# NILINET_RFT.net
KiCad netlist of a schematic drawn in Altium Designer
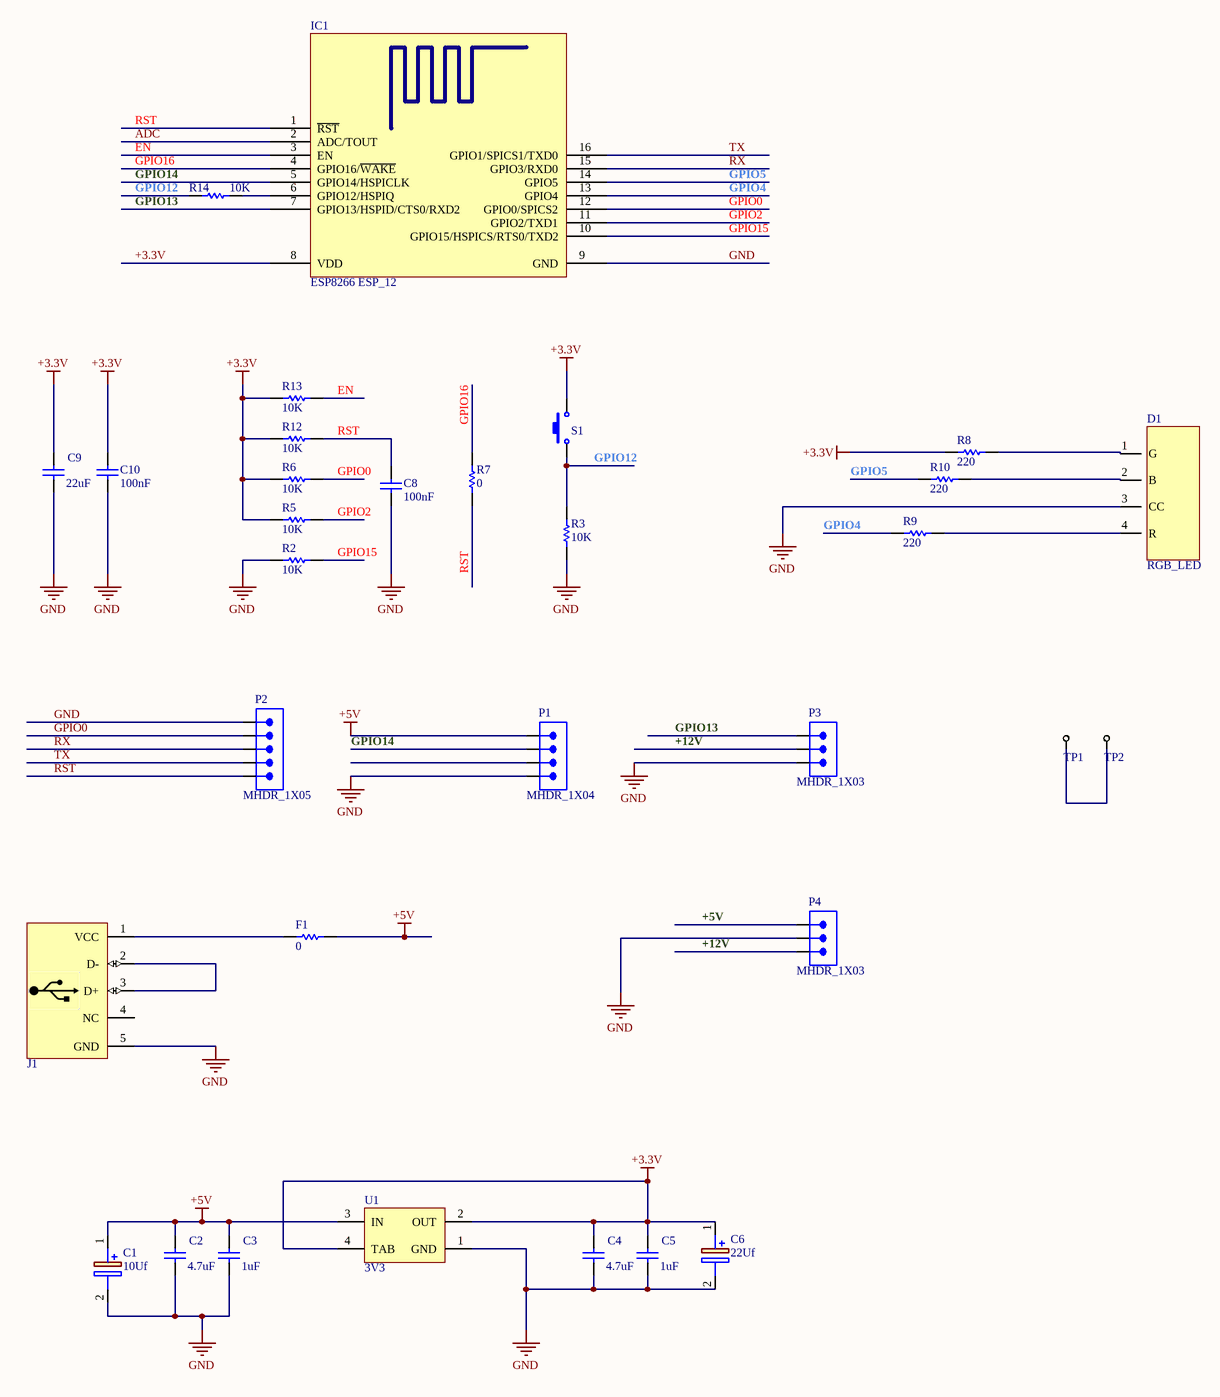
[diagram p0: NILINET_RFT.SchDoc]

(export (version "E")
  (design (tool "Eeschema 10.0.6"))
  (components
    (comp (ref "C1")
      (value "10Uf")
      (footprint "SamacSys:UWT(4X5.4)")
      (description "Capacitor Polarised")
      (fields
        (field (name "MANUFACTURER_PART_NUMBER") "UWT1C100MCL1GB")
        (field (name "MOUSER PART NUMBER") "647-UWT1C100MCL1B")
      )
      (libsource (lib "*") (part "UWT1C100MCL1GB"))
    )
    (comp (ref "C2")
      (value "4.7uF")
      (footprint "CAP0805")
      (description "TOTAL CAPACITOR SMD PACK")
      (fields (field (name "DESIGNER") "Abbas Basereh"))
      (libsource (lib "Altium") (part "CAP SMD PACKAGE"))
    )
    (comp (ref "C3")
      (value "1uF")
      (footprint "CAP0805")
      (description "TOTAL CAPACITOR SMD PACK")
      (fields (field (name "DESIGNER") "Abbas Basereh"))
      (libsource (lib "Altium") (part "CAP SMD PACKAGE"))
    )
    (comp (ref "C4")
      (value "4.7uF")
      (footprint "CAP0805")
      (description "TOTAL CAPACITOR SMD PACK")
      (fields (field (name "DESIGNER") "Abbas Basereh"))
      (libsource (lib "Altium") (part "CAP SMD PACKAGE"))
    )
    (comp (ref "C5")
      (value "1uF")
      (footprint "CAP0805")
      (description "TOTAL CAPACITOR SMD PACK")
      (fields (field (name "DESIGNER") "Abbas Basereh"))
      (libsource (lib "Altium") (part "CAP SMD PACKAGE"))
    )
    (comp (ref "C6")
      (value "22Uf")
      (footprint "SamacSys:UWT(4X5.4)")
      (description "Capacitor Polarised")
      (fields
        (field (name "MANUFACTURER_PART_NUMBER") "UWT1C100MCL1GB")
        (field (name "MOUSER PART NUMBER") "647-UWT1C100MCL1B")
      )
      (libsource (lib "*") (part "UWT1C100MCL1GB"))
    )
    (comp (ref "C8")
      (value "100nF")
      (footprint "CAP0805")
      (description "TOTAL CAPACITOR SMD PACK")
      (fields (field (name "DESIGNER") "Abbas Basereh"))
      (libsource (lib "Altium") (part "CAP SMD PACKAGE"))
    )
    (comp (ref "C9")
      (value "22uF")
      (footprint "CAP0805")
      (description "TOTAL CAPACITOR SMD PACK")
      (fields (field (name "DESIGNER") "Abbas Basereh"))
      (libsource (lib "Altium") (part "CAP SMD PACKAGE"))
    )
    (comp (ref "C10")
      (value "100nF")
      (footprint "CAP0805")
      (description "TOTAL CAPACITOR SMD PACK")
      (fields (field (name "DESIGNER") "Abbas Basereh"))
      (libsource (lib "Altium") (part "CAP SMD PACKAGE"))
    )
    (comp (ref "D1") (value "RGB_LED") (footprint "RGB_LED") (libsource (lib "RGB_LED") (part "RGB_LED")))
    (comp (ref "F1")
      (value "0")
      (footprint "RES0805")
      (description "TOTAL SMD RESISTOR PACK")
      (fields (field (name "DESIGNER") "Abbas Basereh"))
      (libsource (lib "Altium") (part "RES SMD PACKAGE"))
    )
    (comp (ref "IC1")
      (value "ESP8266 ESP_12")
      (footprint "ESP8266 ESP_12")
      (description "ESP8266 ESP-12")
      (fields (field (name "PUBLISHER") "Cynetik Group") (field (name "LATESTREVIEWER") "Zion Blue"))
      (libsource (lib "ESP8266") (part "ESP8266 ESP_12"))
    )
    (comp (ref "J1")
      (value "USB Connector")
      (footprint "MicroUSB111")
      (description "USB Connector MICRO-B Type")
      (fields (field (name "DESIGNER") "ABBAS BASEREH") (field (name "PUBLISHER") "ABBAS BASEREH"))
      (libsource (lib "Altium") (part "USB MICRO"))
    )
    (comp (ref "P1")
      (value "MHDR_1X04")
      (footprint "MHDR1X04-254P")
      (description "Male Header 1X04")
      (libsource (lib "Sockets And Connectors") (part "MHDR_1X04"))
    )
    (comp (ref "P2")
      (value "MHDR_1X05")
      (footprint "MHDR1X05-254P")
      (description "Male Header 1X05")
      (libsource (lib "Sockets And Connectors") (part "MHDR_1X05"))
    )
    (comp (ref "P3")
      (value "MHDR_1X03")
      (footprint "MHDR1X03-254P")
      (description "Male Header 1X03")
      (libsource (lib "Sockets And Connectors") (part "MHDR_1X03"))
    )
    (comp (ref "P4")
      (value "MHDR_1X03")
      (footprint "MHDR1X03-254P")
      (description "Male Header 1X03")
      (libsource (lib "Sockets And Connectors") (part "MHDR_1X03"))
    )
    (comp (ref "R2")
      (value "10K")
      (footprint "RES0805")
      (description "TOTAL SMD RESISTOR PACK")
      (fields (field (name "DESIGNER") "Abbas Basereh"))
      (libsource (lib "Altium") (part "RES SMD PACKAGE"))
    )
    (comp (ref "R3")
      (value "10K")
      (footprint "RES0805")
      (description "TOTAL SMD RESISTOR PACK")
      (fields (field (name "DESIGNER") "Abbas Basereh"))
      (libsource (lib "Altium") (part "RES SMD PACKAGE"))
    )
    (comp (ref "R5")
      (value "10K")
      (footprint "RES0805")
      (description "TOTAL SMD RESISTOR PACK")
      (fields (field (name "DESIGNER") "Abbas Basereh"))
      (libsource (lib "Altium") (part "RES SMD PACKAGE"))
    )
    (comp (ref "R6")
      (value "10K")
      (footprint "RES0805")
      (description "TOTAL SMD RESISTOR PACK")
      (fields (field (name "DESIGNER") "Abbas Basereh"))
      (libsource (lib "Altium") (part "RES SMD PACKAGE"))
    )
    (comp (ref "R7")
      (value "0")
      (footprint "RES0805")
      (description "TOTAL SMD RESISTOR PACK")
      (fields (field (name "DESIGNER") "Abbas Basereh"))
      (libsource (lib "Altium") (part "RES SMD PACKAGE"))
    )
    (comp (ref "R8")
      (value "220")
      (footprint "RES0805")
      (description "TOTAL SMD RESISTOR PACK")
      (fields (field (name "DESIGNER") "Abbas Basereh"))
      (libsource (lib "Altium") (part "RES SMD PACKAGE"))
    )
    (comp (ref "R9")
      (value "220")
      (footprint "RES0805")
      (description "TOTAL SMD RESISTOR PACK")
      (fields (field (name "DESIGNER") "Abbas Basereh"))
      (libsource (lib "Altium") (part "RES SMD PACKAGE"))
    )
    (comp (ref "R10")
      (value "220")
      (footprint "RES0805")
      (description "TOTAL SMD RESISTOR PACK")
      (fields (field (name "DESIGNER") "Abbas Basereh"))
      (libsource (lib "Altium") (part "RES SMD PACKAGE"))
    )
    (comp (ref "R12")
      (value "10K")
      (footprint "RES0805")
      (description "TOTAL SMD RESISTOR PACK")
      (fields (field (name "DESIGNER") "Abbas Basereh"))
      (libsource (lib "Altium") (part "RES SMD PACKAGE"))
    )
    (comp (ref "R13")
      (value "10K")
      (footprint "RES0805")
      (description "TOTAL SMD RESISTOR PACK")
      (fields (field (name "DESIGNER") "Abbas Basereh"))
      (libsource (lib "Altium") (part "RES SMD PACKAGE"))
    )
    (comp (ref "R14")
      (value "10K")
      (footprint "RES0805")
      (description "TOTAL SMD RESISTOR PACK")
      (fields (field (name "DESIGNER") "Abbas Basereh"))
      (libsource (lib "Altium") (part "RES SMD PACKAGE"))
    )
    (comp (ref "S1")
      (value "Switch PB")
      (footprint "SwitchRight")
      (description "Push Button Switch")
      (libsource (lib "Altium") (part "Switch PB"))
    )
    (comp (ref "TP1")
      (value "Test Point")
      (footprint "Test Point")
      (libsource (lib "My Library") (part "Test Point"))
    )
    (comp (ref "TP2")
      (value "Test Point")
      (footprint "Test Point")
      (libsource (lib "My Library") (part "Test Point"))
    )
    (comp (ref "U1")
      (value "3V3")
      (footprint "SOT223")
      (description "x.x Volt, 800mA Low-Dropout Linear Regulator, 4-pin SOT-223")
      (fields (field (name "DESIGNER") "Ali Hafizi"))
      (libsource (lib "Altium") (part "AMS1117-x.x"))
    )
  )
  (nets
    (net (code "1") (name "+3.3V") (class "Default")
      (node (ref "C10") (pin "2") (pinfunction "2_2") (pintype "passive"))
      (node (ref "C4") (pin "2") (pinfunction "2_2") (pintype "passive"))
      (node (ref "C5") (pin "2") (pinfunction "2_2") (pintype "passive"))
      (node (ref "C6") (pin "1") (pinfunction "+_1") (pintype "passive"))
      (node (ref "C9") (pin "2") (pinfunction "2_2") (pintype "passive"))
      (node (ref "IC1") (pin "8") (pinfunction "VDD_8") (pintype "passive"))
      (node (ref "R12") (pin "2") (pinfunction "2_2") (pintype "passive"))
      (node (ref "R13") (pin "2") (pinfunction "2_2") (pintype "passive"))
      (node (ref "R5") (pin "2") (pinfunction "2_2") (pintype "passive"))
      (node (ref "R6") (pin "2") (pinfunction "2_2") (pintype "passive"))
      (node (ref "R8") (pin "1") (pinfunction "1_1") (pintype "passive"))
      (node (ref "S1") (pin "2") (pinfunction "2_2") (pintype "passive"))
      (node (ref "U1") (pin "2") (pinfunction "OUT_2") (pintype "power_in"))
      (node (ref "U1") (pin "4") (pinfunction "TAB_4") (pintype "power_in"))
    )
    (net (code "2") (name "+5V") (class "Default")
      (node (ref "C1") (pin "1") (pinfunction "+_1") (pintype "passive"))
      (node (ref "C2") (pin "2") (pinfunction "2_2") (pintype "passive"))
      (node (ref "C3") (pin "2") (pinfunction "2_2") (pintype "passive"))
      (node (ref "F1") (pin "1") (pinfunction "1_1") (pintype "passive"))
      (node (ref "P1") (pin "1") (pinfunction "1_1") (pintype "passive"))
      (node (ref "P4") (pin "1") (pinfunction "1_1") (pintype "passive"))
      (node (ref "U1") (pin "3") (pinfunction "IN_3") (pintype "power_in"))
    )
    (net (code "3") (name "/+12V") (class "Default")
      (node (ref "P3") (pin "2") (pinfunction "2_2") (pintype "passive"))
      (node (ref "P4") (pin "3") (pinfunction "3_3") (pintype "passive"))
    )
    (net (code "4") (name "/ADC") (class "Default")
      (node (ref "IC1") (pin "2") (pinfunction "ADC/TOUT_2") (pintype "passive"))
    )
    (net (code "5") (name "/EN") (class "Default")
      (node (ref "IC1") (pin "3") (pinfunction "EN_3") (pintype "passive"))
      (node (ref "R13") (pin "1") (pinfunction "1_1") (pintype "passive"))
    )
    (net (code "6") (name "/GPIO0") (class "Default")
      (node (ref "IC1") (pin "12") (pinfunction "GPIO0/SPICS2_12") (pintype "passive"))
      (node (ref "P2") (pin "2") (pinfunction "2_2") (pintype "passive"))
      (node (ref "R6") (pin "1") (pinfunction "1_1") (pintype "passive"))
    )
    (net (code "7") (name "/GPIO2") (class "Default")
      (node (ref "IC1") (pin "11") (pinfunction "GPIO2/TXD1_11") (pintype "passive"))
      (node (ref "R5") (pin "1") (pinfunction "1_1") (pintype "passive"))
    )
    (net (code "8") (name "/GPIO4") (class "Default")
      (node (ref "IC1") (pin "13") (pinfunction "GPIO4_13") (pintype "passive"))
      (node (ref "R9") (pin "1") (pinfunction "1_1") (pintype "passive"))
    )
    (net (code "9") (name "/GPIO5") (class "Default")
      (node (ref "IC1") (pin "14") (pinfunction "GPIO5_14") (pintype "passive"))
      (node (ref "R10") (pin "1") (pinfunction "1_1") (pintype "passive"))
    )
    (net (code "10") (name "/GPIO12") (class "Default")
      (node (ref "R14") (pin "2") (pinfunction "2_2") (pintype "passive"))
      (node (ref "R3") (pin "1") (pinfunction "1_1") (pintype "passive"))
      (node (ref "S1") (pin "1") (pinfunction "1_1") (pintype "passive"))
    )
    (net (code "11") (name "/GPIO13") (class "Default")
      (node (ref "IC1") (pin "7") (pinfunction "GPIO13/HSPID/CTS0/RXD2_7") (pintype "passive"))
      (node (ref "P3") (pin "1") (pinfunction "1_1") (pintype "passive"))
    )
    (net (code "12") (name "/GPIO14") (class "Default")
      (node (ref "IC1") (pin "5") (pinfunction "GPIO14/HSPICLK_5") (pintype "passive"))
      (node (ref "P1") (pin "2") (pinfunction "2_2") (pintype "passive"))
    )
    (net (code "13") (name "/GPIO15") (class "Default")
      (node (ref "IC1") (pin "10") (pinfunction "GPIO15/HSPICS/RTS0/TXD2_10") (pintype "passive"))
      (node (ref "R2") (pin "1") (pinfunction "1_1") (pintype "passive"))
    )
    (net (code "14") (name "/GPIO16") (class "Default")
      (node (ref "IC1") (pin "4") (pinfunction "GPIO16/~{WAKE}_4") (pintype "passive"))
      (node (ref "R7") (pin "1") (pinfunction "1_1") (pintype "passive"))
    )
    (net (code "15") (name "/RST") (class "Default")
      (node (ref "C8") (pin "2") (pinfunction "2_2") (pintype "passive"))
      (node (ref "IC1") (pin "1") (pinfunction "~{RST}_1") (pintype "passive"))
      (node (ref "P2") (pin "5") (pinfunction "5_5") (pintype "passive"))
      (node (ref "R12") (pin "1") (pinfunction "1_1") (pintype "passive"))
      (node (ref "R7") (pin "2") (pinfunction "2_2") (pintype "passive"))
    )
    (net (code "16") (name "/RX") (class "Default")
      (node (ref "IC1") (pin "15") (pinfunction "GPIO3/RXD0_15") (pintype "passive"))
      (node (ref "P2") (pin "3") (pinfunction "3_3") (pintype "passive"))
    )
    (net (code "17") (name "/TX") (class "Default")
      (node (ref "IC1") (pin "16") (pinfunction "GPIO1/SPICS1/TXD0_16") (pintype "passive"))
      (node (ref "P2") (pin "4") (pinfunction "4_4") (pintype "passive"))
    )
    (net (code "18") (name "GND") (class "Default")
      (node (ref "C1") (pin "2") (pinfunction "-_2") (pintype "passive"))
      (node (ref "C10") (pin "1") (pinfunction "1_1") (pintype "passive"))
      (node (ref "C2") (pin "1") (pinfunction "1_1") (pintype "passive"))
      (node (ref "C3") (pin "1") (pinfunction "1_1") (pintype "passive"))
      (node (ref "C4") (pin "1") (pinfunction "1_1") (pintype "passive"))
      (node (ref "C5") (pin "1") (pinfunction "1_1") (pintype "passive"))
      (node (ref "C6") (pin "2") (pinfunction "-_2") (pintype "passive"))
      (node (ref "C8") (pin "1") (pinfunction "1_1") (pintype "passive"))
      (node (ref "C9") (pin "1") (pinfunction "1_1") (pintype "passive"))
      (node (ref "D1") (pin "3") (pinfunction "CC_3") (pintype "passive"))
      (node (ref "IC1") (pin "9") (pinfunction "GND_9") (pintype "passive"))
      (node (ref "J1") (pin "5") (pinfunction "GND_5") (pintype "power_in"))
      (node (ref "P1") (pin "4") (pinfunction "4_4") (pintype "passive"))
      (node (ref "P2") (pin "1") (pinfunction "1_1") (pintype "passive"))
      (node (ref "P3") (pin "3") (pinfunction "3_3") (pintype "passive"))
      (node (ref "P4") (pin "2") (pinfunction "2_2") (pintype "passive"))
      (node (ref "R2") (pin "2") (pinfunction "2_2") (pintype "passive"))
      (node (ref "R3") (pin "2") (pinfunction "2_2") (pintype "passive"))
      (node (ref "U1") (pin "1") (pinfunction "GND_1") (pintype "power_in"))
    )
    (net (code "19") (name "Net-(D1-B)") (class "Default")
      (node (ref "D1") (pin "2") (pinfunction "B_2") (pintype "passive"))
      (node (ref "R10") (pin "2") (pinfunction "2_2") (pintype "passive"))
    )
    (net (code "20") (name "Net-(D1-G)") (class "Default")
      (node (ref "D1") (pin "1") (pinfunction "G_1") (pintype "passive"))
      (node (ref "R8") (pin "2") (pinfunction "2_2") (pintype "passive"))
    )
    (net (code "21") (name "Net-(D1-R)") (class "Default")
      (node (ref "D1") (pin "4") (pinfunction "R_4") (pintype "passive"))
      (node (ref "R9") (pin "2") (pinfunction "2_2") (pintype "passive"))
    )
    (net (code "22") (name "Net-(IC1-GPIO12{slash}HSPIQ)") (class "Default")
      (node (ref "IC1") (pin "6") (pinfunction "GPIO12/HSPIQ_6") (pintype "passive"))
      (node (ref "R14") (pin "1") (pinfunction "1_1") (pintype "passive"))
    )
    (net (code "23") (name "Net-(J1-D+)") (class "Default")
      (node (ref "J1") (pin "2") (pinfunction "D-_2") (pintype "bidirectional"))
      (node (ref "J1") (pin "3") (pinfunction "D+_3") (pintype "bidirectional"))
    )
    (net (code "24") (name "Net-(J1-VCC)") (class "Default")
      (node (ref "F1") (pin "2") (pinfunction "2_2") (pintype "passive"))
      (node (ref "J1") (pin "1") (pinfunction "VCC_1") (pintype "power_in"))
    )
    (net (code "25") (name "Net-(TP1-T)") (class "Default")
      (node (ref "TP1") (pin "1") (pinfunction "T_1") (pintype "passive"))
      (node (ref "TP2") (pin "1") (pinfunction "T_1") (pintype "passive"))
    )
    (net (code "26") (name "unconnected-(J1-NC-Pad4)") (class "Default")
      (node (ref "J1") (pin "4") (pinfunction "NC_4") (pintype "passive"))
    )
    (net (code "27") (name "unconnected-(P1-Pad3)") (class "Default")
      (node (ref "P1") (pin "3") (pinfunction "3_3") (pintype "passive"))
    )
  )
)
